# 3V3_LDO.net
KiCad netlist of a schematic drawn in Altium Designer
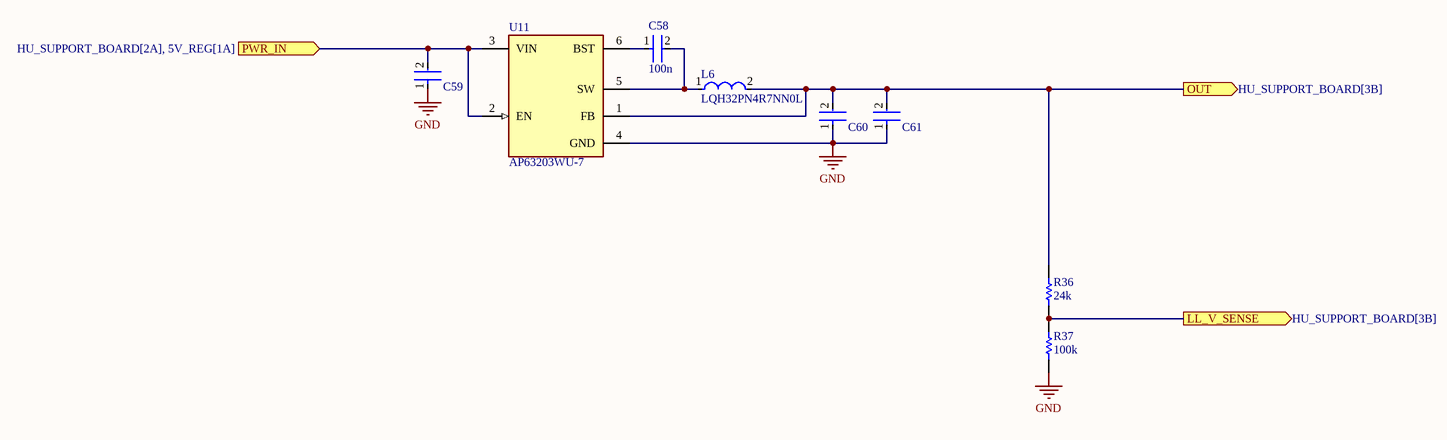
[diagram p0: 3V3_LDO.SchDoc]

(export (version "E")
  (design (tool "Eeschema 10.0.6"))
  (components
    (comp (ref "C58")
      (value "100n")
      (footprint "FP-0402-L_1_0_0_05-W_0_5-IPC_A")
      (description "LARGE PADS, 0402 CAP, CHANGE COMMENT TO MATCH REAL P/N")
      (libsource (lib "Space Concordia") (part "b4654b650e69147ec39a6b967a45e02"))
    )
    (comp (ref "C59")
      (value "GRM21BR61E226ME44L")
      (footprint "FP-GRM21B-0_2-e0_2_0_7-IPC_B")
      (description "Chip Multilayer Ceramic Capacitors for General Purpose, 0805, 22uF, X5R, 15%, 20%, 25V")
      (fields (field (name "TOLERANCE") "20%") (field (name "VOLTAGE") "25V"))
      (libsource (lib "Altium Content Vault") (part "b4654b650e69147ec39a6b967a45e02"))
    )
    (comp (ref "C60")
      (value "GRM21BR61E226ME44L")
      (footprint "FP-GRM21B-0_2-e0_2_0_7-IPC_B")
      (description "Chip Multilayer Ceramic Capacitors for General Purpose, 0805, 22uF, X5R, 15%, 20%, 25V")
      (fields (field (name "TOLERANCE") "20%") (field (name "VOLTAGE") "25V"))
      (libsource (lib "Altium Content Vault") (part "b4654b650e69147ec39a6b967a45e02"))
    )
    (comp (ref "C61")
      (value "GRM21BR61E226ME44L")
      (footprint "FP-GRM21B-0_2-e0_2_0_7-IPC_B")
      (description "Chip Multilayer Ceramic Capacitors for General Purpose, 0805, 22uF, X5R, 15%, 20%, 25V")
      (fields (field (name "TOLERANCE") "20%") (field (name "VOLTAGE") "25V"))
      (libsource (lib "Altium Content Vault") (part "b4654b650e69147ec39a6b967a45e02"))
    )
    (comp (ref "L6")
      (value "LQH32PN4R7NN0L")
      (footprint "FP-LQH32PB_N0-MFG")
      (description "Wire Wound Ferrite Inductor for Power Lines 4.7μH ±30% 0.216Ω 1000mA 1210")
      (fields (field (name "TOLERANCE") "30%"))
      (libsource (lib "Altium Content Vault") (part "725321dda6339637d4d059423bc1c3c"))
    )
    (comp (ref "R36")
      (value "24k")
      (footprint "R0603B")
      (description "Resistor")
      (libsource (lib "Space Concordia") (part "Resistor"))
    )
    (comp (ref "R37")
      (value "100k")
      (footprint "R0603B")
      (description "Resistor")
      (libsource (lib "Space Concordia") (part "Resistor"))
    )
    (comp (ref "U11")
      (value "AP63203WU-7")
      (footprint "FP-TSOT26-MFG")
      (description "IC REG BUCK 3.3V 2A TSOT26")
      (fields
        (field (name "MANUFACTURER") "Diodes Inc.")
        (field (name "OCTOPART") "https://octopart.com/ap63203wu-7-diodes+inc.-98099550")
      )
      (libsource (lib "Altium Content Vault") (part "0e61c2974d7114b43f01ef96ae2e524"))
    )
  )
  (nets
    (net (code "1") (name "/LL_V_SENSE") (class "Default")
      (node (ref "R36") (pin "1") (pinfunction "1_1") (pintype "passive"))
      (node (ref "R37") (pin "2") (pinfunction "2_2") (pintype "passive"))
    )
    (net (code "2") (name "/OUT") (class "Default")
      (node (ref "C60") (pin "2") (pinfunction "2_2") (pintype "passive"))
      (node (ref "C61") (pin "2") (pinfunction "2_2") (pintype "passive"))
      (node (ref "L6") (pin "2") (pinfunction "2_2") (pintype "passive"))
      (node (ref "R36") (pin "2") (pinfunction "2_2") (pintype "passive"))
      (node (ref "U11") (pin "1") (pinfunction "FB_1") (pintype "passive"))
    )
    (net (code "3") (name "/PWR_IN") (class "Default")
      (node (ref "C59") (pin "2") (pinfunction "2_2") (pintype "passive"))
      (node (ref "U11") (pin "2") (pinfunction "EN_2") (pintype "input"))
      (node (ref "U11") (pin "3") (pinfunction "VIN_3") (pintype "power_in"))
    )
    (net (code "4") (name "GND") (class "Default")
      (node (ref "C59") (pin "1") (pinfunction "1_1") (pintype "passive"))
      (node (ref "C60") (pin "1") (pinfunction "1_1") (pintype "passive"))
      (node (ref "C61") (pin "1") (pinfunction "1_1") (pintype "passive"))
      (node (ref "R37") (pin "1") (pinfunction "1_1") (pintype "passive"))
      (node (ref "U11") (pin "4") (pinfunction "GND_4") (pintype "power_in"))
    )
    (net (code "5") (name "Net-(U11-BST)") (class "Default")
      (node (ref "C58") (pin "1") (pinfunction "1_1") (pintype "passive"))
      (node (ref "U11") (pin "6") (pinfunction "BST_6") (pintype "passive"))
    )
    (net (code "6") (name "Net-(U11-SW)") (class "Default")
      (node (ref "C58") (pin "2") (pinfunction "2_2") (pintype "passive"))
      (node (ref "L6") (pin "1") (pinfunction "1_1") (pintype "passive"))
      (node (ref "U11") (pin "5") (pinfunction "SW_5") (pintype "passive"))
    )
  )
)
